# loader.net
KiCad netlist of a schematic drawn in EAGLE
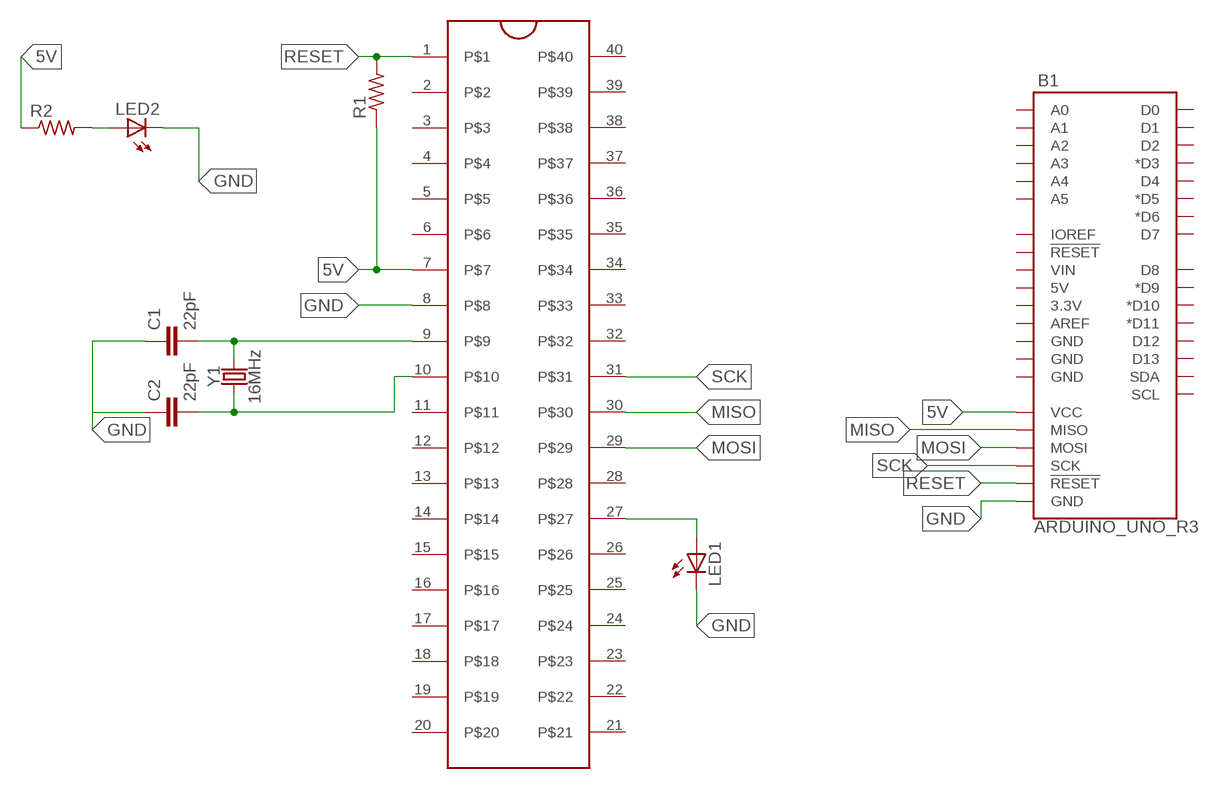
[diagram p0: schematic, sheet 1]

(export (version "E")
  (design (tool "Eeschema 10.0.6"))
  (components
    (comp (ref "B1")
      (value "ARDUINO_UNO_R3")
      (footprint "eagle-import:ARDUINO_R3")
      (libsource (lib "eagle-import") (part "ARDUINO_UNO_R3"))
    )
    (comp (ref "C1")
      (value "22pF")
      (footprint "eagle-import:CAP-PTH-2.54")
      (libsource (lib "eagle-import") (part "22PF-PTH-2.54MM-200V-5%"))
    )
    (comp (ref "C2")
      (value "22pF")
      (footprint "eagle-import:CAP-PTH-2.54")
      (libsource (lib "eagle-import") (part "22PF-PTH-2.54MM-200V-5%"))
    )
    (comp (ref "LED1")
      (value "LED5MM")
      (footprint "eagle-import:LED5MM")
      (libsource (lib "eagle-import") (part "LED5MM"))
    )
    (comp (ref "LED2")
      (value "LED5MM")
      (footprint "eagle-import:LED5MM")
      (libsource (lib "eagle-import") (part "LED5MM"))
    )
    (comp (ref "R1")
      (value "R-US_0309/10")
      (footprint "eagle-import:0309_10")
      (libsource (lib "eagle-import") (part "R-US_0309/10"))
    )
    (comp (ref "R2")
      (value "R-US_0309/10")
      (footprint "eagle-import:0309_10")
      (libsource (lib "eagle-import") (part "R-US_0309/10"))
    )
    (comp (ref "U$1")
      (value "ZIFSOCKET-40-6DIL40-6-ZIF_SOCKET")
      (footprint "eagle-import:DIL40-6-ZIF_SOCKET")
      (libsource (lib "eagle-import") (part "ZIFSOCKET-40-6DIL40-6-ZIF_SOCKET"))
    )
    (comp (ref "Y1")
      (value "16MHz")
      (footprint "eagle-import:HC49US")
      (libsource (lib "eagle-import") (part "CRYSTAL-16MHZPTH-HC49US"))
    )
  )
  (nets
    (net (code "1") (name "5V") (class "Default")
      (node (ref "B1") (pin "VCC") (pinfunction "VCC_VCC") (pintype "bidirectional"))
      (node (ref "R1") (pin "1") (pinfunction "1_1") (pintype "passive"))
      (node (ref "R2") (pin "1") (pinfunction "1_1") (pintype "passive"))
      (node (ref "U$1") (pin "7") (pinfunction "P$7_7") (pintype "bidirectional"))
    )
    (net (code "2") (name "GND") (class "Default")
      (node (ref "B1") (pin "GND@1") (pinfunction "GND_GND@1") (pintype "bidirectional"))
      (node (ref "C1") (pin "1") (pinfunction "1_1") (pintype "passive"))
      (node (ref "C2") (pin "1") (pinfunction "1_1") (pintype "passive"))
      (node (ref "LED1") (pin "K") (pinfunction "C_K") (pintype "passive"))
      (node (ref "LED2") (pin "K") (pinfunction "C_K") (pintype "passive"))
      (node (ref "U$1") (pin "8") (pinfunction "P$8_8") (pintype "bidirectional"))
    )
    (net (code "3") (name "MISO") (class "Default")
      (node (ref "B1") (pin "MISO") (pinfunction "MISO_MISO") (pintype "bidirectional"))
      (node (ref "U$1") (pin "30") (pinfunction "P$30_30") (pintype "bidirectional"))
    )
    (net (code "4") (name "MOSI") (class "Default")
      (node (ref "B1") (pin "MOSI") (pinfunction "MOSI_MOSI") (pintype "bidirectional"))
      (node (ref "U$1") (pin "29") (pinfunction "P$29_29") (pintype "bidirectional"))
    )
    (net (code "5") (name "Net-(LED2-PadA)") (class "Default")
      (node (ref "LED2") (pin "A") (pinfunction "A_A") (pintype "passive"))
      (node (ref "R2") (pin "2") (pinfunction "2_2") (pintype "passive"))
    )
    (net (code "6") (name "Net-(U$1-P$9)") (class "Default")
      (node (ref "C1") (pin "2") (pinfunction "2_2") (pintype "passive"))
      (node (ref "U$1") (pin "9") (pinfunction "P$9_9") (pintype "bidirectional"))
      (node (ref "Y1") (pin "2") (pinfunction "2_2") (pintype "passive"))
    )
    (net (code "7") (name "Net-(U$1-P$10)") (class "Default")
      (node (ref "C2") (pin "2") (pinfunction "2_2") (pintype "passive"))
      (node (ref "U$1") (pin "10") (pinfunction "P$10_10") (pintype "bidirectional"))
      (node (ref "Y1") (pin "1") (pinfunction "1_1") (pintype "passive"))
    )
    (net (code "8") (name "Net-(U$1-P$27)") (class "Default")
      (node (ref "LED1") (pin "A") (pinfunction "A_A") (pintype "passive"))
      (node (ref "U$1") (pin "27") (pinfunction "P$27_27") (pintype "bidirectional"))
    )
    (net (code "9") (name "RESET") (class "Default")
      (node (ref "B1") (pin "RESET@2") (pinfunction "~{RESET}_RESET@2") (pintype "bidirectional"))
      (node (ref "R1") (pin "2") (pinfunction "2_2") (pintype "passive"))
      (node (ref "U$1") (pin "1") (pinfunction "P$1_1") (pintype "bidirectional"))
    )
    (net (code "10") (name "SCK") (class "Default")
      (node (ref "B1") (pin "SCK") (pinfunction "SCK_SCK") (pintype "bidirectional"))
      (node (ref "U$1") (pin "31") (pinfunction "P$31_31") (pintype "bidirectional"))
    )
    (net (code "11") (name "unconnected-(B1-*D3-PadD3)") (class "Default")
      (node (ref "B1") (pin "D3") (pinfunction "*D3_D3") (pintype "bidirectional"))
    )
    (net (code "12") (name "unconnected-(B1-*D5-PadD5)") (class "Default")
      (node (ref "B1") (pin "D5") (pinfunction "*D5_D5") (pintype "bidirectional"))
    )
    (net (code "13") (name "unconnected-(B1-*D6-PadD6)") (class "Default")
      (node (ref "B1") (pin "D6") (pinfunction "*D6_D6") (pintype "bidirectional"))
    )
    (net (code "14") (name "unconnected-(B1-*D9-PadD9)") (class "Default")
      (node (ref "B1") (pin "D9") (pinfunction "*D9_D9") (pintype "bidirectional"))
    )
    (net (code "15") (name "unconnected-(B1-*D10-PadD10)") (class "Default")
      (node (ref "B1") (pin "D10") (pinfunction "*D10_D10") (pintype "bidirectional"))
    )
    (net (code "16") (name "unconnected-(B1-*D11-PadD11)") (class "Default")
      (node (ref "B1") (pin "D11") (pinfunction "*D11_D11") (pintype "bidirectional"))
    )
    (net (code "17") (name "unconnected-(B1-GND-PadGND@2)") (class "Default")
      (node (ref "B1") (pin "GND@2") (pinfunction "GND_GND@2") (pintype "bidirectional"))
    )
    (net (code "18") (name "unconnected-(B1-GND-PadGND@3)") (class "Default")
      (node (ref "B1") (pin "GND@3") (pinfunction "GND_GND@3") (pintype "bidirectional"))
    )
    (net (code "19") (name "unconnected-(B1-GND-PadGND@4)") (class "Default")
      (node (ref "B1") (pin "GND@4") (pinfunction "GND_GND@4") (pintype "bidirectional"))
    )
    (net (code "20") (name "unconnected-(B1-Pad3.3V)") (class "Default")
      (node (ref "B1") (pin "3.3V") (pinfunction "3.3V_3.3V") (pintype "bidirectional"))
    )
    (net (code "21") (name "unconnected-(B1-Pad5V)") (class "Default")
      (node (ref "B1") (pin "5V") (pinfunction "5V_5V") (pintype "bidirectional"))
    )
    (net (code "22") (name "unconnected-(B1-PadA0)") (class "Default")
      (node (ref "B1") (pin "A0") (pinfunction "A0_A0") (pintype "bidirectional"))
    )
    (net (code "23") (name "unconnected-(B1-PadA1)") (class "Default")
      (node (ref "B1") (pin "A1") (pinfunction "A1_A1") (pintype "bidirectional"))
    )
    (net (code "24") (name "unconnected-(B1-PadA2)") (class "Default")
      (node (ref "B1") (pin "A2") (pinfunction "A2_A2") (pintype "bidirectional"))
    )
    (net (code "25") (name "unconnected-(B1-PadA3)") (class "Default")
      (node (ref "B1") (pin "A3") (pinfunction "A3_A3") (pintype "bidirectional"))
    )
    (net (code "26") (name "unconnected-(B1-PadA4)") (class "Default")
      (node (ref "B1") (pin "A4") (pinfunction "A4_A4") (pintype "bidirectional"))
    )
    (net (code "27") (name "unconnected-(B1-PadA5)") (class "Default")
      (node (ref "B1") (pin "A5") (pinfunction "A5_A5") (pintype "bidirectional"))
    )
    (net (code "28") (name "unconnected-(B1-PadAREF)") (class "Default")
      (node (ref "B1") (pin "AREF") (pinfunction "AREF_AREF") (pintype "bidirectional"))
    )
    (net (code "29") (name "unconnected-(B1-PadD0)") (class "Default")
      (node (ref "B1") (pin "D0") (pinfunction "D0_D0") (pintype "bidirectional"))
    )
    (net (code "30") (name "unconnected-(B1-PadD1)") (class "Default")
      (node (ref "B1") (pin "D1") (pinfunction "D1_D1") (pintype "bidirectional"))
    )
    (net (code "31") (name "unconnected-(B1-PadD2)") (class "Default")
      (node (ref "B1") (pin "D2") (pinfunction "D2_D2") (pintype "bidirectional"))
    )
    (net (code "32") (name "unconnected-(B1-PadD4)") (class "Default")
      (node (ref "B1") (pin "D4") (pinfunction "D4_D4") (pintype "bidirectional"))
    )
    (net (code "33") (name "unconnected-(B1-PadD7)") (class "Default")
      (node (ref "B1") (pin "D7") (pinfunction "D7_D7") (pintype "bidirectional"))
    )
    (net (code "34") (name "unconnected-(B1-PadD8)") (class "Default")
      (node (ref "B1") (pin "D8") (pinfunction "D8_D8") (pintype "bidirectional"))
    )
    (net (code "35") (name "unconnected-(B1-PadD12)") (class "Default")
      (node (ref "B1") (pin "D12") (pinfunction "D12_D12") (pintype "bidirectional"))
    )
    (net (code "36") (name "unconnected-(B1-PadD13)") (class "Default")
      (node (ref "B1") (pin "D13") (pinfunction "D13_D13") (pintype "bidirectional"))
    )
    (net (code "37") (name "unconnected-(B1-PadIOREF)") (class "Default")
      (node (ref "B1") (pin "IOREF") (pinfunction "IOREF_IOREF") (pintype "bidirectional"))
    )
    (net (code "38") (name "unconnected-(B1-PadSCL)") (class "Default")
      (node (ref "B1") (pin "SCL") (pinfunction "SCL_SCL") (pintype "bidirectional"))
    )
    (net (code "39") (name "unconnected-(B1-PadSDA)") (class "Default")
      (node (ref "B1") (pin "SDA") (pinfunction "SDA_SDA") (pintype "bidirectional"))
    )
    (net (code "40") (name "unconnected-(B1-PadVIN)") (class "Default")
      (node (ref "B1") (pin "VIN") (pinfunction "VIN_VIN") (pintype "bidirectional"))
    )
    (net (code "41") (name "unconnected-(B1-~{RESET}-PadRESET@1)") (class "Default")
      (node (ref "B1") (pin "RESET@1") (pinfunction "~{RESET}_RESET@1") (pintype "bidirectional"))
    )
    (net (code "42") (name "unconnected-(U$1-P$2-Pad2)") (class "Default")
      (node (ref "U$1") (pin "2") (pinfunction "P$2_2") (pintype "bidirectional"))
    )
    (net (code "43") (name "unconnected-(U$1-P$3-Pad3)") (class "Default")
      (node (ref "U$1") (pin "3") (pinfunction "P$3_3") (pintype "bidirectional"))
    )
    (net (code "44") (name "unconnected-(U$1-P$4-Pad4)") (class "Default")
      (node (ref "U$1") (pin "4") (pinfunction "P$4_4") (pintype "bidirectional"))
    )
    (net (code "45") (name "unconnected-(U$1-P$5-Pad5)") (class "Default")
      (node (ref "U$1") (pin "5") (pinfunction "P$5_5") (pintype "bidirectional"))
    )
    (net (code "46") (name "unconnected-(U$1-P$6-Pad6)") (class "Default")
      (node (ref "U$1") (pin "6") (pinfunction "P$6_6") (pintype "bidirectional"))
    )
    (net (code "47") (name "unconnected-(U$1-P$11-Pad11)") (class "Default")
      (node (ref "U$1") (pin "11") (pinfunction "P$11_11") (pintype "bidirectional"))
    )
    (net (code "48") (name "unconnected-(U$1-P$12-Pad12)") (class "Default")
      (node (ref "U$1") (pin "12") (pinfunction "P$12_12") (pintype "bidirectional"))
    )
    (net (code "49") (name "unconnected-(U$1-P$13-Pad13)") (class "Default")
      (node (ref "U$1") (pin "13") (pinfunction "P$13_13") (pintype "bidirectional"))
    )
    (net (code "50") (name "unconnected-(U$1-P$14-Pad14)") (class "Default")
      (node (ref "U$1") (pin "14") (pinfunction "P$14_14") (pintype "bidirectional"))
    )
    (net (code "51") (name "unconnected-(U$1-P$15-Pad15)") (class "Default")
      (node (ref "U$1") (pin "15") (pinfunction "P$15_15") (pintype "bidirectional"))
    )
    (net (code "52") (name "unconnected-(U$1-P$16-Pad16)") (class "Default")
      (node (ref "U$1") (pin "16") (pinfunction "P$16_16") (pintype "bidirectional"))
    )
    (net (code "53") (name "unconnected-(U$1-P$17-Pad17)") (class "Default")
      (node (ref "U$1") (pin "17") (pinfunction "P$17_17") (pintype "bidirectional"))
    )
    (net (code "54") (name "unconnected-(U$1-P$18-Pad18)") (class "Default")
      (node (ref "U$1") (pin "18") (pinfunction "P$18_18") (pintype "bidirectional"))
    )
    (net (code "55") (name "unconnected-(U$1-P$19-Pad19)") (class "Default")
      (node (ref "U$1") (pin "19") (pinfunction "P$19_19") (pintype "bidirectional"))
    )
    (net (code "56") (name "unconnected-(U$1-P$20-Pad20)") (class "Default")
      (node (ref "U$1") (pin "20") (pinfunction "P$20_20") (pintype "bidirectional"))
    )
    (net (code "57") (name "unconnected-(U$1-P$21-Pad21)") (class "Default")
      (node (ref "U$1") (pin "21") (pinfunction "P$21_21") (pintype "bidirectional"))
    )
    (net (code "58") (name "unconnected-(U$1-P$22-Pad22)") (class "Default")
      (node (ref "U$1") (pin "22") (pinfunction "P$22_22") (pintype "bidirectional"))
    )
    (net (code "59") (name "unconnected-(U$1-P$23-Pad23)") (class "Default")
      (node (ref "U$1") (pin "23") (pinfunction "P$23_23") (pintype "bidirectional"))
    )
    (net (code "60") (name "unconnected-(U$1-P$24-Pad24)") (class "Default")
      (node (ref "U$1") (pin "24") (pinfunction "P$24_24") (pintype "bidirectional"))
    )
    (net (code "61") (name "unconnected-(U$1-P$25-Pad25)") (class "Default")
      (node (ref "U$1") (pin "25") (pinfunction "P$25_25") (pintype "bidirectional"))
    )
    (net (code "62") (name "unconnected-(U$1-P$26-Pad26)") (class "Default")
      (node (ref "U$1") (pin "26") (pinfunction "P$26_26") (pintype "bidirectional"))
    )
    (net (code "63") (name "unconnected-(U$1-P$28-Pad28)") (class "Default")
      (node (ref "U$1") (pin "28") (pinfunction "P$28_28") (pintype "bidirectional"))
    )
    (net (code "64") (name "unconnected-(U$1-P$32-Pad32)") (class "Default")
      (node (ref "U$1") (pin "32") (pinfunction "P$32_32") (pintype "bidirectional"))
    )
    (net (code "65") (name "unconnected-(U$1-P$33-Pad33)") (class "Default")
      (node (ref "U$1") (pin "33") (pinfunction "P$33_33") (pintype "bidirectional"))
    )
    (net (code "66") (name "unconnected-(U$1-P$34-Pad34)") (class "Default")
      (node (ref "U$1") (pin "34") (pinfunction "P$34_34") (pintype "bidirectional"))
    )
    (net (code "67") (name "unconnected-(U$1-P$35-Pad35)") (class "Default")
      (node (ref "U$1") (pin "35") (pinfunction "P$35_35") (pintype "bidirectional"))
    )
    (net (code "68") (name "unconnected-(U$1-P$36-Pad36)") (class "Default")
      (node (ref "U$1") (pin "36") (pinfunction "P$36_36") (pintype "bidirectional"))
    )
    (net (code "69") (name "unconnected-(U$1-P$37-Pad37)") (class "Default")
      (node (ref "U$1") (pin "37") (pinfunction "P$37_37") (pintype "bidirectional"))
    )
    (net (code "70") (name "unconnected-(U$1-P$38-Pad38)") (class "Default")
      (node (ref "U$1") (pin "38") (pinfunction "P$38_38") (pintype "bidirectional"))
    )
    (net (code "71") (name "unconnected-(U$1-P$39-Pad39)") (class "Default")
      (node (ref "U$1") (pin "39") (pinfunction "P$39_39") (pintype "bidirectional"))
    )
    (net (code "72") (name "unconnected-(U$1-P$40-Pad40)") (class "Default")
      (node (ref "U$1") (pin "40") (pinfunction "P$40_40") (pintype "bidirectional"))
    )
  )
)
